# Socket_Hole.net
KiCad netlist of a schematic drawn in Altium Designer
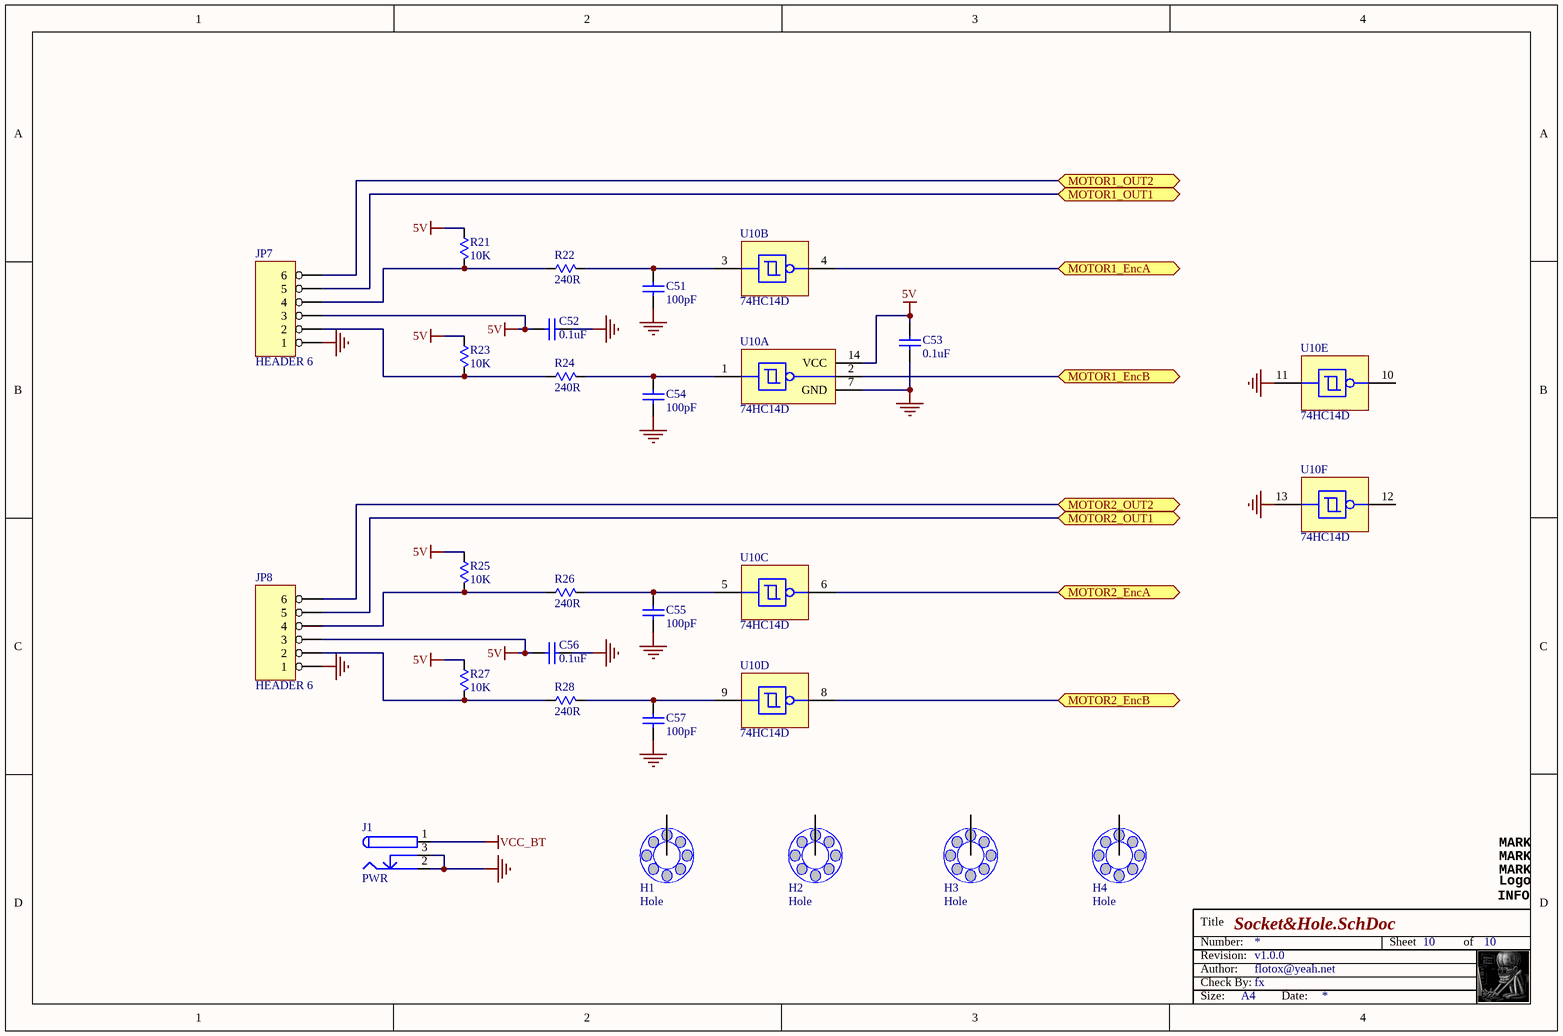
[diagram p0: Socket&Hole.SchDoc]

(export (version "E")
  (design (tool "Eeschema 10.0.6"))
  (components
    (comp (ref "C51")
      (value "100pF")
      (footprint "C0603-S")
      (description "Capacitor")
      (libsource (lib "Passive Components Class") (part "CAP"))
    )
    (comp (ref "C52")
      (value "0.1uF")
      (footprint "C0603-S")
      (description "Capacitor")
      (libsource (lib "Passive Components Class") (part "CAP"))
    )
    (comp (ref "C53")
      (value "0.1uF")
      (footprint "C0603-S")
      (description "Capacitor")
      (libsource (lib "Passive Components Class") (part "CAP"))
    )
    (comp (ref "C54")
      (value "100pF")
      (footprint "C0603-S")
      (description "Capacitor")
      (libsource (lib "Passive Components Class") (part "CAP"))
    )
    (comp (ref "C55")
      (value "100pF")
      (footprint "C0603-S")
      (description "Capacitor")
      (libsource (lib "Passive Components Class") (part "CAP"))
    )
    (comp (ref "C56")
      (value "0.1uF")
      (footprint "C0603-S")
      (description "Capacitor")
      (libsource (lib "Passive Components Class") (part "CAP"))
    )
    (comp (ref "C57")
      (value "100pF")
      (footprint "C0603-S")
      (description "Capacitor")
      (libsource (lib "Passive Components Class") (part "CAP"))
    )
    (comp (ref "H1")
      (value "Hole")
      (footprint "HT-M3-S")
      (description "Mounting holes")
      (libsource (lib "FX Class") (part "Hole"))
    )
    (comp (ref "H2")
      (value "Hole")
      (footprint "HT-M3-S")
      (description "Mounting holes")
      (libsource (lib "FX Class") (part "Hole"))
    )
    (comp (ref "H3")
      (value "Hole")
      (footprint "HT-M3-S")
      (description "Mounting holes")
      (libsource (lib "FX Class") (part "Hole"))
    )
    (comp (ref "H4")
      (value "Hole")
      (footprint "HT-M3-S")
      (description "Mounting holes")
      (libsource (lib "FX Class") (part "Hole"))
    )
    (comp (ref "INFO1")
      (value "INFO")
      (footprint "FX_DESIGN_INFO")
      (libsource (lib "FX Class") (part "INFO"))
    )
    (comp (ref "J1") (value "PWR") (footprint "POWER-A") (libsource (lib "Connector Class") (part "PWR")))
    (comp (ref "JP7")
      (value "HEADER 6")
      (footprint "WHDR2.0X6")
      (libsource (lib "Connector Class") (part "HEADER 6"))
    )
    (comp (ref "JP8")
      (value "HEADER 6")
      (footprint "WHDR2.0X6")
      (libsource (lib "Connector Class") (part "HEADER 6"))
    )
    (comp (ref "LG1") (value "LOGO") (footprint "Hat_Logo") (libsource (lib "FX Class") (part "LOGO")))
    (comp (ref "MARK1") (value "MARK") (footprint "MARK-S") (libsource (lib "FX Class") (part "MARK")))
    (comp (ref "MARK2") (value "MARK") (footprint "MARK-S") (libsource (lib "FX Class") (part "MARK")))
    (comp (ref "MARK3") (value "MARK") (footprint "MARK-S") (libsource (lib "FX Class") (part "MARK")))
    (comp (ref "R21")
      (value "10K")
      (footprint "R0603-S")
      (description "Resistor")
      (libsource (lib "Passive Components Class") (part "RES"))
    )
    (comp (ref "R22")
      (value "240R")
      (footprint "R0603-S")
      (description "Resistor")
      (libsource (lib "Passive Components Class") (part "RES"))
    )
    (comp (ref "R23")
      (value "10K")
      (footprint "R0603-S")
      (description "Resistor")
      (libsource (lib "Passive Components Class") (part "RES"))
    )
    (comp (ref "R24")
      (value "240R")
      (footprint "R0603-S")
      (description "Resistor")
      (libsource (lib "Passive Components Class") (part "RES"))
    )
    (comp (ref "R25")
      (value "10K")
      (footprint "R0603-S")
      (description "Resistor")
      (libsource (lib "Passive Components Class") (part "RES"))
    )
    (comp (ref "R26")
      (value "240R")
      (footprint "R0603-S")
      (description "Resistor")
      (libsource (lib "Passive Components Class") (part "RES"))
    )
    (comp (ref "R27")
      (value "10K")
      (footprint "R0603-S")
      (description "Resistor")
      (libsource (lib "Passive Components Class") (part "RES"))
    )
    (comp (ref "R28")
      (value "240R")
      (footprint "R0603-S")
      (description "Resistor")
      (libsource (lib "Passive Components Class") (part "RES"))
    )
    (comp (ref "U10")
      (value "74HC14D")
      (footprint "SO14-150")
      (description "Hex inverting Schmitt trigger")
      (libsource (lib "Logic Class") (part "74HC14D"))
    )
  )
  (nets
    (net (code "1") (name "/MOTOR1_EncA") (class "Default")
      (node (ref "U10") (pin "4") (pinfunction "Y_4") (pintype "passive"))
    )
    (net (code "2") (name "/MOTOR1_EncB") (class "Default")
      (node (ref "U10") (pin "2") (pinfunction "Y_2") (pintype "passive"))
    )
    (net (code "3") (name "/MOTOR1_OUT1") (class "Default")
      (node (ref "JP7") (pin "5") (pinfunction "5_5") (pintype "passive"))
    )
    (net (code "4") (name "/MOTOR1_OUT2") (class "Default")
      (node (ref "JP7") (pin "6") (pinfunction "6_6") (pintype "passive"))
    )
    (net (code "5") (name "/MOTOR2_EncA") (class "Default")
      (node (ref "U10") (pin "6") (pinfunction "Y_6") (pintype "passive"))
    )
    (net (code "6") (name "/MOTOR2_EncB") (class "Default")
      (node (ref "U10") (pin "8") (pinfunction "Y_8") (pintype "passive"))
    )
    (net (code "7") (name "/MOTOR2_OUT1") (class "Default")
      (node (ref "JP8") (pin "5") (pinfunction "5_5") (pintype "passive"))
    )
    (net (code "8") (name "/MOTOR2_OUT2") (class "Default")
      (node (ref "JP8") (pin "6") (pinfunction "6_6") (pintype "passive"))
    )
    (net (code "9") (name "5V") (class "Default")
      (node (ref "C52") (pin "1") (pinfunction "1_1") (pintype "passive"))
      (node (ref "C53") (pin "1") (pinfunction "1_1") (pintype "passive"))
      (node (ref "C56") (pin "1") (pinfunction "1_1") (pintype "passive"))
      (node (ref "JP7") (pin "3") (pinfunction "3_3") (pintype "passive"))
      (node (ref "JP8") (pin "3") (pinfunction "3_3") (pintype "passive"))
      (node (ref "R21") (pin "2") (pinfunction "2_2") (pintype "passive"))
      (node (ref "R23") (pin "2") (pinfunction "2_2") (pintype "passive"))
      (node (ref "R25") (pin "2") (pinfunction "2_2") (pintype "passive"))
      (node (ref "R27") (pin "2") (pinfunction "2_2") (pintype "passive"))
      (node (ref "U10") (pin "14") (pinfunction "VCC_14") (pintype "passive"))
    )
    (net (code "10") (name "GND") (class "Default")
      (node (ref "C51") (pin "1") (pinfunction "1_1") (pintype "passive"))
      (node (ref "C52") (pin "2") (pinfunction "2_2") (pintype "passive"))
      (node (ref "C53") (pin "2") (pinfunction "2_2") (pintype "passive"))
      (node (ref "C54") (pin "1") (pinfunction "1_1") (pintype "passive"))
      (node (ref "C55") (pin "1") (pinfunction "1_1") (pintype "passive"))
      (node (ref "C56") (pin "2") (pinfunction "2_2") (pintype "passive"))
      (node (ref "C57") (pin "1") (pinfunction "1_1") (pintype "passive"))
      (node (ref "J1") (pin "2") (pinfunction "2_2") (pintype "power_in"))
      (node (ref "J1") (pin "3") (pinfunction "3_3") (pintype "power_in"))
      (node (ref "JP7") (pin "1") (pinfunction "1_1") (pintype "passive"))
      (node (ref "JP8") (pin "1") (pinfunction "1_1") (pintype "passive"))
      (node (ref "U10") (pin "11") (pinfunction "A_11") (pintype "passive"))
      (node (ref "U10") (pin "13") (pinfunction "A_13") (pintype "passive"))
      (node (ref "U10") (pin "7") (pinfunction "GND_7") (pintype "passive"))
    )
    (net (code "11") (name "Net-(JP7-Pad2)") (class "Default")
      (node (ref "JP7") (pin "2") (pinfunction "2_2") (pintype "passive"))
      (node (ref "R23") (pin "1") (pinfunction "1_1") (pintype "passive"))
      (node (ref "R24") (pin "2") (pinfunction "2_2") (pintype "passive"))
    )
    (net (code "12") (name "Net-(JP7-Pad4)") (class "Default")
      (node (ref "JP7") (pin "4") (pinfunction "4_4") (pintype "passive"))
      (node (ref "R21") (pin "1") (pinfunction "1_1") (pintype "passive"))
      (node (ref "R22") (pin "2") (pinfunction "2_2") (pintype "passive"))
    )
    (net (code "13") (name "Net-(JP8-Pad2)") (class "Default")
      (node (ref "JP8") (pin "2") (pinfunction "2_2") (pintype "passive"))
      (node (ref "R27") (pin "1") (pinfunction "1_1") (pintype "passive"))
      (node (ref "R28") (pin "2") (pinfunction "2_2") (pintype "passive"))
    )
    (net (code "14") (name "Net-(JP8-Pad4)") (class "Default")
      (node (ref "JP8") (pin "4") (pinfunction "4_4") (pintype "passive"))
      (node (ref "R25") (pin "1") (pinfunction "1_1") (pintype "passive"))
      (node (ref "R26") (pin "2") (pinfunction "2_2") (pintype "passive"))
    )
    (net (code "15") (name "Net-(U10A-A)") (class "Default")
      (node (ref "C54") (pin "2") (pinfunction "2_2") (pintype "passive"))
      (node (ref "R24") (pin "1") (pinfunction "1_1") (pintype "passive"))
      (node (ref "U10") (pin "1") (pinfunction "A_1") (pintype "passive"))
    )
    (net (code "16") (name "Net-(U10B-A)") (class "Default")
      (node (ref "C51") (pin "2") (pinfunction "2_2") (pintype "passive"))
      (node (ref "R22") (pin "1") (pinfunction "1_1") (pintype "passive"))
      (node (ref "U10") (pin "3") (pinfunction "A_3") (pintype "passive"))
    )
    (net (code "17") (name "Net-(U10C-A)") (class "Default")
      (node (ref "C55") (pin "2") (pinfunction "2_2") (pintype "passive"))
      (node (ref "R26") (pin "1") (pinfunction "1_1") (pintype "passive"))
      (node (ref "U10") (pin "5") (pinfunction "A_5") (pintype "passive"))
    )
    (net (code "18") (name "Net-(U10D-A)") (class "Default")
      (node (ref "C57") (pin "2") (pinfunction "2_2") (pintype "passive"))
      (node (ref "R28") (pin "1") (pinfunction "1_1") (pintype "passive"))
      (node (ref "U10") (pin "9") (pinfunction "A_9") (pintype "passive"))
    )
    (net (code "19") (name "VCC_BT") (class "Default")
      (node (ref "J1") (pin "1") (pinfunction "1_1") (pintype "power_in"))
    )
    (net (code "20") (name "unconnected-(H1-Pad1)") (class "Default")
      (node (ref "H1") (pin "1") (pintype "passive"))
    )
    (net (code "21") (name "unconnected-(H2-Pad1)") (class "Default")
      (node (ref "H2") (pin "1") (pintype "passive"))
    )
    (net (code "22") (name "unconnected-(H3-Pad1)") (class "Default")
      (node (ref "H3") (pin "1") (pintype "passive"))
    )
    (net (code "23") (name "unconnected-(H4-Pad1)") (class "Default")
      (node (ref "H4") (pin "1") (pintype "passive"))
    )
    (net (code "24") (name "unconnected-(U10E-Y-Pad10)") (class "Default")
      (node (ref "U10") (pin "10") (pinfunction "Y_10") (pintype "passive"))
    )
    (net (code "25") (name "unconnected-(U10F-Y-Pad12)") (class "Default")
      (node (ref "U10") (pin "12") (pinfunction "Y_12") (pintype "passive"))
    )
  )
)
